# TopSheet.net
KiCad netlist of a schematic drawn in Altium Designer
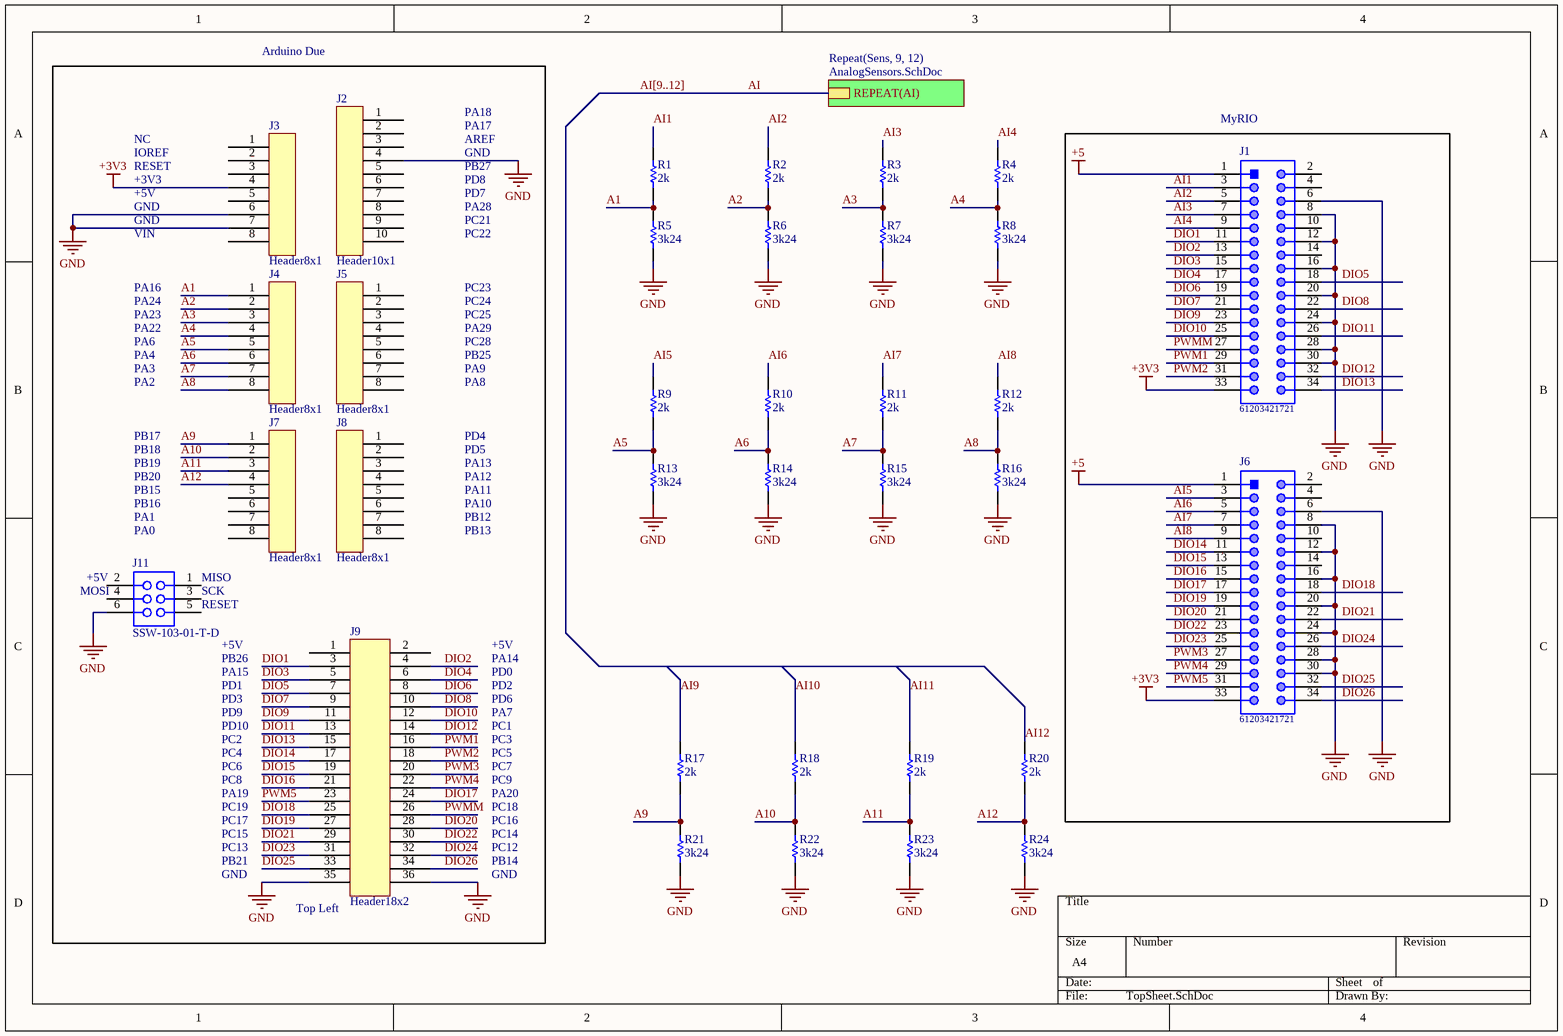
[diagram p0: TopSheet.SchDoc]

(export (version "E")
  (design (tool "Eeschema 10.0.6"))
  (components
    (comp (ref "J1")
      (value "61203421721")
      (footprint "61203421721")
      (description "Male Box Header WR-BHD, THT, Angled, pitch 2.54 mm, 34 pins")
      (fields (field (name "MANUFACTURER") "Wurth Elektronik") (field (name "PUBLISHER") "WurthElektronik"))
      (libsource (lib "Altium Content Vault") (part "WE-CN-2P-M-R34"))
    )
    (comp (ref "J2")
      (value "Header10x1")
      (footprint "Header10x1")
      (libsource (lib "Schlib1") (part "Header10x1"))
    )
    (comp (ref "J3") (value "Header8x1") (footprint "Header8x1") (libsource (lib "") (part "Header8x1_1")))
    (comp (ref "J4") (value "Header8x1") (footprint "Header8x1") (libsource (lib "") (part "Header8x1_1")))
    (comp (ref "J5")
      (value "Header8x1")
      (footprint "Header8x1")
      (libsource (lib "Schlib1") (part "Header8x1"))
    )
    (comp (ref "J6")
      (value "61203421721")
      (footprint "61203421721")
      (description "Male Box Header WR-BHD, THT, Angled, pitch 2.54 mm, 34 pins")
      (fields (field (name "MANUFACTURER") "Wurth Elektronik") (field (name "PUBLISHER") "WurthElektronik"))
      (libsource (lib "Altium Content Vault") (part "WE-CN-2P-M-R34"))
    )
    (comp (ref "J7") (value "Header8x1") (footprint "Header8x1") (libsource (lib "") (part "Header8x1_1")))
    (comp (ref "J8")
      (value "Header8x1")
      (footprint "Header8x1")
      (libsource (lib "Schlib1") (part "Header8x1"))
    )
    (comp (ref "J9")
      (value "Header18x2")
      (footprint "Header18x2")
      (libsource (lib "Schlib1") (part "Header18x2"))
    )
    (comp (ref "J11")
      (value "SSW-103-01-T-D")
      (footprint "SMTC-SSW-103-01-X-D")
      (description "SQ Post Socket, Through-hole, Vertical, -55 to 105 degC, 2.54 mm Pitch, 6-Pin, Female, RoHS")
      (fields (field (name "MANUFACTURER") "Samtec"))
      (libsource (lib "Altium Content Vault") (part "SMTC-SSW-103-01-X-D"))
    )
    (comp (ref "R1")
      (value "2k")
      (footprint "RESC1608X55X25LL10T15")
      (description "Chip Resistor, 2 KOhm, +/- 1%, 50 V, -55 to 155 degC, 0603 (1608 Metric), RoHS, Tape and Reel")
      (fields (field (name "TOLERANCE") "±1%") (field (name "MANUFACTURER") "Yageo"))
      (libsource (lib "Altium Content Vault") (part "RES-2"))
    )
    (comp (ref "R2")
      (value "2k")
      (footprint "RESC1608X55X25LL10T15")
      (description "Chip Resistor, 2 KOhm, +/- 1%, 50 V, -55 to 155 degC, 0603 (1608 Metric), RoHS, Tape and Reel")
      (fields (field (name "TOLERANCE") "±1%") (field (name "MANUFACTURER") "Yageo"))
      (libsource (lib "Altium Content Vault") (part "RES-2"))
    )
    (comp (ref "R3")
      (value "2k")
      (footprint "RESC1608X55X25LL10T15")
      (description "Chip Resistor, 2 KOhm, +/- 1%, 50 V, -55 to 155 degC, 0603 (1608 Metric), RoHS, Tape and Reel")
      (fields (field (name "TOLERANCE") "±1%") (field (name "MANUFACTURER") "Yageo"))
      (libsource (lib "Altium Content Vault") (part "RES-2"))
    )
    (comp (ref "R4")
      (value "2k")
      (footprint "RESC1608X55X25LL10T15")
      (description "Chip Resistor, 2 KOhm, +/- 1%, 50 V, -55 to 155 degC, 0603 (1608 Metric), RoHS, Tape and Reel")
      (fields (field (name "TOLERANCE") "±1%") (field (name "MANUFACTURER") "Yageo"))
      (libsource (lib "Altium Content Vault") (part "RES-2"))
    )
    (comp (ref "R5")
      (value "3k24")
      (footprint "RESC1608X55X25LL10T15")
      (fields (field (name "TOLERANCE") "±1%") (field (name "MANUFACTURER") "Yageo"))
      (libsource (lib "Altium Content Vault") (part "RES-2"))
    )
    (comp (ref "R6")
      (value "3k24")
      (footprint "RESC1608X55X25LL10T15")
      (fields (field (name "TOLERANCE") "±1%") (field (name "MANUFACTURER") "Yageo"))
      (libsource (lib "Altium Content Vault") (part "RES-2"))
    )
    (comp (ref "R7")
      (value "3k24")
      (footprint "RESC1608X55X25LL10T15")
      (fields (field (name "TOLERANCE") "±1%") (field (name "MANUFACTURER") "Yageo"))
      (libsource (lib "Altium Content Vault") (part "RES-2"))
    )
    (comp (ref "R8")
      (value "3k24")
      (footprint "RESC1608X55X25LL10T15")
      (fields (field (name "TOLERANCE") "±1%") (field (name "MANUFACTURER") "Yageo"))
      (libsource (lib "Altium Content Vault") (part "RES-2"))
    )
    (comp (ref "R9")
      (value "2k")
      (footprint "RESC1608X55X25LL10T15")
      (description "Chip Resistor, 2 KOhm, +/- 1%, 50 V, -55 to 155 degC, 0603 (1608 Metric), RoHS, Tape and Reel")
      (fields (field (name "TOLERANCE") "±1%") (field (name "MANUFACTURER") "Yageo"))
      (libsource (lib "Altium Content Vault") (part "RES-2"))
    )
    (comp (ref "R10")
      (value "2k")
      (footprint "RESC1608X55X25LL10T15")
      (description "Chip Resistor, 2 KOhm, +/- 1%, 50 V, -55 to 155 degC, 0603 (1608 Metric), RoHS, Tape and Reel")
      (fields (field (name "TOLERANCE") "±1%") (field (name "MANUFACTURER") "Yageo"))
      (libsource (lib "Altium Content Vault") (part "RES-2"))
    )
    (comp (ref "R11")
      (value "2k")
      (footprint "RESC1608X55X25LL10T15")
      (description "Chip Resistor, 2 KOhm, +/- 1%, 50 V, -55 to 155 degC, 0603 (1608 Metric), RoHS, Tape and Reel")
      (fields (field (name "TOLERANCE") "±1%") (field (name "MANUFACTURER") "Yageo"))
      (libsource (lib "Altium Content Vault") (part "RES-2"))
    )
    (comp (ref "R12")
      (value "2k")
      (footprint "RESC1608X55X25LL10T15")
      (description "Chip Resistor, 2 KOhm, +/- 1%, 50 V, -55 to 155 degC, 0603 (1608 Metric), RoHS, Tape and Reel")
      (fields (field (name "TOLERANCE") "±1%") (field (name "MANUFACTURER") "Yageo"))
      (libsource (lib "Altium Content Vault") (part "RES-2"))
    )
    (comp (ref "R13")
      (value "3k24")
      (footprint "RESC1608X55X25LL10T15")
      (fields (field (name "TOLERANCE") "±1%") (field (name "MANUFACTURER") "Yageo"))
      (libsource (lib "Altium Content Vault") (part "RES-2"))
    )
    (comp (ref "R14")
      (value "3k24")
      (footprint "RESC1608X55X25LL10T15")
      (fields (field (name "TOLERANCE") "±1%") (field (name "MANUFACTURER") "Yageo"))
      (libsource (lib "Altium Content Vault") (part "RES-2"))
    )
    (comp (ref "R15")
      (value "3k24")
      (footprint "RESC1608X55X25LL10T15")
      (fields (field (name "TOLERANCE") "±1%") (field (name "MANUFACTURER") "Yageo"))
      (libsource (lib "Altium Content Vault") (part "RES-2"))
    )
    (comp (ref "R16")
      (value "3k24")
      (footprint "RESC1608X55X25LL10T15")
      (fields (field (name "TOLERANCE") "±1%") (field (name "MANUFACTURER") "Yageo"))
      (libsource (lib "Altium Content Vault") (part "RES-2"))
    )
    (comp (ref "R17")
      (value "2k")
      (footprint "RESC1608X55X25LL10T15")
      (description "Chip Resistor, 2 KOhm, +/- 1%, 50 V, -55 to 155 degC, 0603 (1608 Metric), RoHS, Tape and Reel")
      (fields (field (name "TOLERANCE") "±1%") (field (name "MANUFACTURER") "Yageo"))
      (libsource (lib "Altium Content Vault") (part "RES-2"))
    )
    (comp (ref "R18")
      (value "2k")
      (footprint "RESC1608X55X25LL10T15")
      (description "Chip Resistor, 2 KOhm, +/- 1%, 50 V, -55 to 155 degC, 0603 (1608 Metric), RoHS, Tape and Reel")
      (fields (field (name "TOLERANCE") "±1%") (field (name "MANUFACTURER") "Yageo"))
      (libsource (lib "Altium Content Vault") (part "RES-2"))
    )
    (comp (ref "R19")
      (value "2k")
      (footprint "RESC1608X55X25LL10T15")
      (description "Chip Resistor, 2 KOhm, +/- 1%, 50 V, -55 to 155 degC, 0603 (1608 Metric), RoHS, Tape and Reel")
      (fields (field (name "TOLERANCE") "±1%") (field (name "MANUFACTURER") "Yageo"))
      (libsource (lib "Altium Content Vault") (part "RES-2"))
    )
    (comp (ref "R20")
      (value "2k")
      (footprint "RESC1608X55X25LL10T15")
      (description "Chip Resistor, 2 KOhm, +/- 1%, 50 V, -55 to 155 degC, 0603 (1608 Metric), RoHS, Tape and Reel")
      (fields (field (name "TOLERANCE") "±1%") (field (name "MANUFACTURER") "Yageo"))
      (libsource (lib "Altium Content Vault") (part "RES-2"))
    )
    (comp (ref "R21")
      (value "3k24")
      (footprint "RESC1608X55X25LL10T15")
      (fields (field (name "TOLERANCE") "±1%") (field (name "MANUFACTURER") "Yageo"))
      (libsource (lib "Altium Content Vault") (part "RES-2"))
    )
    (comp (ref "R22")
      (value "3k24")
      (footprint "RESC1608X55X25LL10T15")
      (fields (field (name "TOLERANCE") "±1%") (field (name "MANUFACTURER") "Yageo"))
      (libsource (lib "Altium Content Vault") (part "RES-2"))
    )
    (comp (ref "R23")
      (value "3k24")
      (footprint "RESC1608X55X25LL10T15")
      (fields (field (name "TOLERANCE") "±1%") (field (name "MANUFACTURER") "Yageo"))
      (libsource (lib "Altium Content Vault") (part "RES-2"))
    )
    (comp (ref "R24")
      (value "3k24")
      (footprint "RESC1608X55X25LL10T15")
      (fields (field (name "TOLERANCE") "±1%") (field (name "MANUFACTURER") "Yageo"))
      (libsource (lib "Altium Content Vault") (part "RES-2"))
    )
  )
  (nets
    (net (code "1") (name "+3V3") (class "Default")
      (node (ref "J1") (pin "33") (pinfunction "33_33") (pintype "passive"))
      (node (ref "J3") (pin "4") (pintype "passive"))
      (node (ref "J6") (pin "33") (pinfunction "33_33") (pintype "passive"))
    )
    (net (code "2") (name "+5") (class "Default")
      (node (ref "J1") (pin "1") (pinfunction "1_1") (pintype "passive"))
      (node (ref "J6") (pin "1") (pinfunction "1_1") (pintype "passive"))
    )
    (net (code "3") (name "/A1") (class "Default")
      (node (ref "J4") (pin "1") (pintype "passive"))
      (node (ref "R1") (pin "1") (pinfunction "1_1") (pintype "passive"))
      (node (ref "R5") (pin "2") (pinfunction "2_2") (pintype "passive"))
    )
    (net (code "4") (name "/A2") (class "Default")
      (node (ref "J4") (pin "2") (pintype "passive"))
      (node (ref "R2") (pin "1") (pinfunction "1_1") (pintype "passive"))
      (node (ref "R6") (pin "2") (pinfunction "2_2") (pintype "passive"))
    )
    (net (code "5") (name "/A3") (class "Default")
      (node (ref "J4") (pin "3") (pintype "passive"))
      (node (ref "R3") (pin "1") (pinfunction "1_1") (pintype "passive"))
      (node (ref "R7") (pin "2") (pinfunction "2_2") (pintype "passive"))
    )
    (net (code "6") (name "/A4") (class "Default")
      (node (ref "J4") (pin "4") (pintype "passive"))
      (node (ref "R4") (pin "1") (pinfunction "1_1") (pintype "passive"))
      (node (ref "R8") (pin "2") (pinfunction "2_2") (pintype "passive"))
    )
    (net (code "7") (name "/A5") (class "Default")
      (node (ref "J4") (pin "5") (pintype "passive"))
      (node (ref "R13") (pin "2") (pinfunction "2_2") (pintype "passive"))
      (node (ref "R9") (pin "1") (pinfunction "1_1") (pintype "passive"))
    )
    (net (code "8") (name "/A6") (class "Default")
      (node (ref "J4") (pin "6") (pintype "passive"))
      (node (ref "R10") (pin "1") (pinfunction "1_1") (pintype "passive"))
      (node (ref "R14") (pin "2") (pinfunction "2_2") (pintype "passive"))
    )
    (net (code "9") (name "/A7") (class "Default")
      (node (ref "J4") (pin "7") (pintype "passive"))
      (node (ref "R11") (pin "1") (pinfunction "1_1") (pintype "passive"))
      (node (ref "R15") (pin "2") (pinfunction "2_2") (pintype "passive"))
    )
    (net (code "10") (name "/A8") (class "Default")
      (node (ref "J4") (pin "8") (pintype "passive"))
      (node (ref "R12") (pin "1") (pinfunction "1_1") (pintype "passive"))
      (node (ref "R16") (pin "2") (pinfunction "2_2") (pintype "passive"))
    )
    (net (code "11") (name "/A9") (class "Default")
      (node (ref "J7") (pin "1") (pintype "passive"))
      (node (ref "R17") (pin "1") (pinfunction "1_1") (pintype "passive"))
      (node (ref "R21") (pin "2") (pinfunction "2_2") (pintype "passive"))
    )
    (net (code "12") (name "/A10") (class "Default")
      (node (ref "J7") (pin "2") (pintype "passive"))
      (node (ref "R18") (pin "1") (pinfunction "1_1") (pintype "passive"))
      (node (ref "R22") (pin "2") (pinfunction "2_2") (pintype "passive"))
    )
    (net (code "13") (name "/A11") (class "Default")
      (node (ref "J7") (pin "3") (pintype "passive"))
      (node (ref "R19") (pin "1") (pinfunction "1_1") (pintype "passive"))
      (node (ref "R23") (pin "2") (pinfunction "2_2") (pintype "passive"))
    )
    (net (code "14") (name "/A12") (class "Default")
      (node (ref "J7") (pin "4") (pintype "passive"))
      (node (ref "R20") (pin "1") (pinfunction "1_1") (pintype "passive"))
      (node (ref "R24") (pin "2") (pinfunction "2_2") (pintype "passive"))
    )
    (net (code "16") (name "/AI1") (class "Default")
      (node (ref "J1") (pin "3") (pinfunction "3_3") (pintype "passive"))
      (node (ref "R1") (pin "2") (pinfunction "2_2") (pintype "passive"))
    )
    (net (code "17") (name "/AI2") (class "Default")
      (node (ref "J1") (pin "5") (pinfunction "5_5") (pintype "passive"))
      (node (ref "R2") (pin "2") (pinfunction "2_2") (pintype "passive"))
    )
    (net (code "18") (name "/AI3") (class "Default")
      (node (ref "J1") (pin "7") (pinfunction "7_7") (pintype "passive"))
      (node (ref "R3") (pin "2") (pinfunction "2_2") (pintype "passive"))
    )
    (net (code "19") (name "/AI4") (class "Default")
      (node (ref "J1") (pin "9") (pinfunction "9_9") (pintype "passive"))
      (node (ref "R4") (pin "2") (pinfunction "2_2") (pintype "passive"))
    )
    (net (code "20") (name "/AI5") (class "Default")
      (node (ref "J6") (pin "3") (pinfunction "3_3") (pintype "passive"))
      (node (ref "R9") (pin "2") (pinfunction "2_2") (pintype "passive"))
    )
    (net (code "21") (name "/AI6") (class "Default")
      (node (ref "J6") (pin "5") (pinfunction "5_5") (pintype "passive"))
      (node (ref "R10") (pin "2") (pinfunction "2_2") (pintype "passive"))
    )
    (net (code "22") (name "/AI7") (class "Default")
      (node (ref "J6") (pin "7") (pinfunction "7_7") (pintype "passive"))
      (node (ref "R11") (pin "2") (pinfunction "2_2") (pintype "passive"))
    )
    (net (code "23") (name "/AI8") (class "Default")
      (node (ref "J6") (pin "9") (pinfunction "9_9") (pintype "passive"))
      (node (ref "R12") (pin "2") (pinfunction "2_2") (pintype "passive"))
    )
    (net (code "24") (name "/AI9") (class "Default")
      (node (ref "R17") (pin "2") (pinfunction "2_2") (pintype "passive"))
    )
    (net (code "25") (name "/AI10") (class "Default")
      (node (ref "R18") (pin "2") (pinfunction "2_2") (pintype "passive"))
    )
    (net (code "26") (name "/AI11") (class "Default")
      (node (ref "R19") (pin "2") (pinfunction "2_2") (pintype "passive"))
    )
    (net (code "27") (name "/AI12") (class "Default")
      (node (ref "R20") (pin "2") (pinfunction "2_2") (pintype "passive"))
    )
    (net (code "29") (name "/DIO1") (class "Default")
      (node (ref "J1") (pin "11") (pinfunction "11_11") (pintype "passive"))
      (node (ref "J9") (pin "3") (pintype "passive"))
    )
    (net (code "30") (name "/DIO2") (class "Default")
      (node (ref "J1") (pin "13") (pinfunction "13_13") (pintype "passive"))
      (node (ref "J9") (pin "4") (pintype "passive"))
    )
    (net (code "31") (name "/DIO3") (class "Default")
      (node (ref "J1") (pin "15") (pinfunction "15_15") (pintype "passive"))
      (node (ref "J9") (pin "5") (pintype "passive"))
    )
    (net (code "32") (name "/DIO4") (class "Default")
      (node (ref "J1") (pin "17") (pinfunction "17_17") (pintype "passive"))
      (node (ref "J9") (pin "6") (pintype "passive"))
    )
    (net (code "33") (name "/DIO5") (class "Default")
      (node (ref "J1") (pin "18") (pinfunction "18_18") (pintype "passive"))
      (node (ref "J9") (pin "7") (pintype "passive"))
    )
    (net (code "34") (name "/DIO6") (class "Default")
      (node (ref "J1") (pin "19") (pinfunction "19_19") (pintype "passive"))
      (node (ref "J9") (pin "8") (pintype "passive"))
    )
    (net (code "35") (name "/DIO7") (class "Default")
      (node (ref "J1") (pin "21") (pinfunction "21_21") (pintype "passive"))
      (node (ref "J9") (pin "9") (pintype "passive"))
    )
    (net (code "36") (name "/DIO8") (class "Default")
      (node (ref "J1") (pin "22") (pinfunction "22_22") (pintype "passive"))
      (node (ref "J9") (pin "10") (pintype "passive"))
    )
    (net (code "37") (name "/DIO9") (class "Default")
      (node (ref "J1") (pin "23") (pinfunction "23_23") (pintype "passive"))
      (node (ref "J9") (pin "11") (pintype "passive"))
    )
    (net (code "38") (name "/DIO10") (class "Default")
      (node (ref "J1") (pin "25") (pinfunction "25_25") (pintype "passive"))
      (node (ref "J9") (pin "12") (pintype "passive"))
    )
    (net (code "39") (name "/DIO11") (class "Default")
      (node (ref "J1") (pin "26") (pinfunction "26_26") (pintype "passive"))
      (node (ref "J9") (pin "13") (pintype "passive"))
    )
    (net (code "40") (name "/DIO12") (class "Default")
      (node (ref "J1") (pin "32") (pinfunction "32_32") (pintype "passive"))
      (node (ref "J9") (pin "14") (pintype "passive"))
    )
    (net (code "41") (name "/DIO13") (class "Default")
      (node (ref "J1") (pin "34") (pinfunction "34_34") (pintype "passive"))
      (node (ref "J9") (pin "15") (pintype "passive"))
    )
    (net (code "42") (name "/DIO14") (class "Default")
      (node (ref "J6") (pin "11") (pinfunction "11_11") (pintype "passive"))
      (node (ref "J9") (pin "17") (pintype "passive"))
    )
    (net (code "43") (name "/DIO15") (class "Default")
      (node (ref "J6") (pin "13") (pinfunction "13_13") (pintype "passive"))
      (node (ref "J9") (pin "19") (pintype "passive"))
    )
    (net (code "44") (name "/DIO16") (class "Default")
      (node (ref "J6") (pin "15") (pinfunction "15_15") (pintype "passive"))
      (node (ref "J9") (pin "21") (pintype "passive"))
    )
    (net (code "45") (name "/DIO17") (class "Default")
      (node (ref "J6") (pin "17") (pinfunction "17_17") (pintype "passive"))
      (node (ref "J9") (pin "24") (pintype "passive"))
    )
    (net (code "46") (name "/DIO18") (class "Default")
      (node (ref "J6") (pin "18") (pinfunction "18_18") (pintype "passive"))
      (node (ref "J9") (pin "25") (pintype "passive"))
    )
    (net (code "47") (name "/DIO19") (class "Default")
      (node (ref "J6") (pin "19") (pinfunction "19_19") (pintype "passive"))
      (node (ref "J9") (pin "27") (pintype "passive"))
    )
    (net (code "48") (name "/DIO20") (class "Default")
      (node (ref "J6") (pin "21") (pinfunction "21_21") (pintype "passive"))
      (node (ref "J9") (pin "28") (pintype "passive"))
    )
    (net (code "49") (name "/DIO21") (class "Default")
      (node (ref "J6") (pin "22") (pinfunction "22_22") (pintype "passive"))
      (node (ref "J9") (pin "29") (pintype "passive"))
    )
    (net (code "50") (name "/DIO22") (class "Default")
      (node (ref "J6") (pin "23") (pinfunction "23_23") (pintype "passive"))
      (node (ref "J9") (pin "30") (pintype "passive"))
    )
    (net (code "51") (name "/DIO23") (class "Default")
      (node (ref "J6") (pin "25") (pinfunction "25_25") (pintype "passive"))
      (node (ref "J9") (pin "31") (pintype "passive"))
    )
    (net (code "52") (name "/DIO24") (class "Default")
      (node (ref "J6") (pin "26") (pinfunction "26_26") (pintype "passive"))
      (node (ref "J9") (pin "32") (pintype "passive"))
    )
    (net (code "53") (name "/DIO25") (class "Default")
      (node (ref "J6") (pin "32") (pinfunction "32_32") (pintype "passive"))
      (node (ref "J9") (pin "33") (pintype "passive"))
    )
    (net (code "54") (name "/DIO26") (class "Default")
      (node (ref "J6") (pin "34") (pinfunction "34_34") (pintype "passive"))
      (node (ref "J9") (pin "34") (pintype "passive"))
    )
    (net (code "55") (name "/PWM1") (class "Default")
      (node (ref "J1") (pin "29") (pinfunction "29_29") (pintype "passive"))
      (node (ref "J9") (pin "16") (pintype "passive"))
    )
    (net (code "56") (name "/PWM2") (class "Default")
      (node (ref "J1") (pin "31") (pinfunction "31_31") (pintype "passive"))
      (node (ref "J9") (pin "18") (pintype "passive"))
    )
    (net (code "57") (name "/PWM3") (class "Default")
      (node (ref "J6") (pin "27") (pinfunction "27_27") (pintype "passive"))
      (node (ref "J9") (pin "20") (pintype "passive"))
    )
    (net (code "58") (name "/PWM4") (class "Default")
      (node (ref "J6") (pin "29") (pinfunction "29_29") (pintype "passive"))
      (node (ref "J9") (pin "22") (pintype "passive"))
    )
    (net (code "59") (name "/PWM5") (class "Default")
      (node (ref "J6") (pin "31") (pinfunction "31_31") (pintype "passive"))
      (node (ref "J9") (pin "23") (pintype "passive"))
    )
    (net (code "60") (name "/PWMM") (class "Default")
      (node (ref "J1") (pin "27") (pinfunction "27_27") (pintype "passive"))
      (node (ref "J9") (pin "26") (pintype "passive"))
    )
    (net (code "61") (name "GND") (class "Default")
      (node (ref "J1") (pin "12") (pinfunction "12_12") (pintype "passive"))
      (node (ref "J1") (pin "16") (pinfunction "16_16") (pintype "passive"))
      (node (ref "J1") (pin "20") (pinfunction "20_20") (pintype "passive"))
      (node (ref "J1") (pin "24") (pinfunction "24_24") (pintype "passive"))
      (node (ref "J1") (pin "28") (pinfunction "28_28") (pintype "passive"))
      (node (ref "J1") (pin "30") (pinfunction "30_30") (pintype "passive"))
      (node (ref "J1") (pin "6") (pinfunction "6_6") (pintype "passive"))
      (node (ref "J1") (pin "8") (pinfunction "8_8") (pintype "passive"))
      (node (ref "J11") (pin "6") (pinfunction "2_6") (pintype "passive"))
      (node (ref "J2") (pin "4") (pintype "passive"))
      (node (ref "J3") (pin "6") (pintype "passive"))
      (node (ref "J3") (pin "7") (pintype "passive"))
      (node (ref "J6") (pin "12") (pinfunction "12_12") (pintype "passive"))
      (node (ref "J6") (pin "16") (pinfunction "16_16") (pintype "passive"))
      (node (ref "J6") (pin "20") (pinfunction "20_20") (pintype "passive"))
      (node (ref "J6") (pin "24") (pinfunction "24_24") (pintype "passive"))
      (node (ref "J6") (pin "28") (pinfunction "28_28") (pintype "passive"))
      (node (ref "J6") (pin "30") (pinfunction "30_30") (pintype "passive"))
      (node (ref "J6") (pin "6") (pinfunction "6_6") (pintype "passive"))
      (node (ref "J6") (pin "8") (pinfunction "8_8") (pintype "passive"))
      (node (ref "J9") (pin "35") (pintype "passive"))
      (node (ref "J9") (pin "36") (pintype "passive"))
      (node (ref "R13") (pin "1") (pinfunction "1_1") (pintype "passive"))
      (node (ref "R14") (pin "1") (pinfunction "1_1") (pintype "passive"))
      (node (ref "R15") (pin "1") (pinfunction "1_1") (pintype "passive"))
      (node (ref "R16") (pin "1") (pinfunction "1_1") (pintype "passive"))
      (node (ref "R21") (pin "1") (pinfunction "1_1") (pintype "passive"))
      (node (ref "R22") (pin "1") (pinfunction "1_1") (pintype "passive"))
      (node (ref "R23") (pin "1") (pinfunction "1_1") (pintype "passive"))
      (node (ref "R24") (pin "1") (pinfunction "1_1") (pintype "passive"))
      (node (ref "R5") (pin "1") (pinfunction "1_1") (pintype "passive"))
      (node (ref "R6") (pin "1") (pinfunction "1_1") (pintype "passive"))
      (node (ref "R7") (pin "1") (pinfunction "1_1") (pintype "passive"))
      (node (ref "R8") (pin "1") (pinfunction "1_1") (pintype "passive"))
    )
    (net (code "62") (name "unconnected-(J1-Pad2)") (class "Default")
      (node (ref "J1") (pin "2") (pinfunction "2_2") (pintype "passive"))
    )
    (net (code "63") (name "unconnected-(J1-Pad4)") (class "Default")
      (node (ref "J1") (pin "4") (pinfunction "4_4") (pintype "passive"))
    )
    (net (code "64") (name "unconnected-(J1-Pad10)") (class "Default")
      (node (ref "J1") (pin "10") (pinfunction "10_10") (pintype "passive"))
    )
    (net (code "65") (name "unconnected-(J1-Pad14)") (class "Default")
      (node (ref "J1") (pin "14") (pinfunction "14_14") (pintype "passive"))
    )
    (net (code "66") (name "unconnected-(J2-Pad1)") (class "Default")
      (node (ref "J2") (pin "1") (pintype "passive"))
    )
    (net (code "67") (name "unconnected-(J2-Pad2)") (class "Default")
      (node (ref "J2") (pin "2") (pintype "passive"))
    )
    (net (code "68") (name "unconnected-(J2-Pad3)") (class "Default")
      (node (ref "J2") (pin "3") (pintype "passive"))
    )
    (net (code "69") (name "unconnected-(J2-Pad5)") (class "Default")
      (node (ref "J2") (pin "5") (pintype "passive"))
    )
    (net (code "70") (name "unconnected-(J2-Pad6)") (class "Default")
      (node (ref "J2") (pin "6") (pintype "passive"))
    )
    (net (code "71") (name "unconnected-(J2-Pad7)") (class "Default")
      (node (ref "J2") (pin "7") (pintype "passive"))
    )
    (net (code "72") (name "unconnected-(J2-Pad8)") (class "Default")
      (node (ref "J2") (pin "8") (pintype "passive"))
    )
    (net (code "73") (name "unconnected-(J2-Pad9)") (class "Default")
      (node (ref "J2") (pin "9") (pintype "passive"))
    )
    (net (code "74") (name "unconnected-(J2-Pad10)") (class "Default")
      (node (ref "J2") (pin "10") (pintype "passive"))
    )
    (net (code "75") (name "unconnected-(J3-Pad1)") (class "Default")
      (node (ref "J3") (pin "1") (pintype "passive"))
    )
    (net (code "76") (name "unconnected-(J3-Pad2)") (class "Default")
      (node (ref "J3") (pin "2") (pintype "passive"))
    )
    (net (code "77") (name "unconnected-(J3-Pad3)") (class "Default")
      (node (ref "J3") (pin "3") (pintype "passive"))
    )
    (net (code "78") (name "unconnected-(J3-Pad5)") (class "Default")
      (node (ref "J3") (pin "5") (pintype "passive"))
    )
    (net (code "79") (name "unconnected-(J3-Pad8)") (class "Default")
      (node (ref "J3") (pin "8") (pintype "passive"))
    )
    (net (code "80") (name "unconnected-(J5-Pad1)") (class "Default")
      (node (ref "J5") (pin "1") (pintype "passive"))
    )
    (net (code "81") (name "unconnected-(J5-Pad2)") (class "Default")
      (node (ref "J5") (pin "2") (pintype "passive"))
    )
    (net (code "82") (name "unconnected-(J5-Pad3)") (class "Default")
      (node (ref "J5") (pin "3") (pintype "passive"))
    )
    (net (code "83") (name "unconnected-(J5-Pad4)") (class "Default")
      (node (ref "J5") (pin "4") (pintype "passive"))
    )
    (net (code "84") (name "unconnected-(J5-Pad5)") (class "Default")
      (node (ref "J5") (pin "5") (pintype "passive"))
    )
    (net (code "85") (name "unconnected-(J5-Pad6)") (class "Default")
      (node (ref "J5") (pin "6") (pintype "passive"))
    )
    (net (code "86") (name "unconnected-(J5-Pad7)") (class "Default")
      (node (ref "J5") (pin "7") (pintype "passive"))
    )
    (net (code "87") (name "unconnected-(J5-Pad8)") (class "Default")
      (node (ref "J5") (pin "8") (pintype "passive"))
    )
    (net (code "88") (name "unconnected-(J6-Pad2)") (class "Default")
      (node (ref "J6") (pin "2") (pinfunction "2_2") (pintype "passive"))
    )
    (net (code "89") (name "unconnected-(J6-Pad4)") (class "Default")
      (node (ref "J6") (pin "4") (pinfunction "4_4") (pintype "passive"))
    )
    (net (code "90") (name "unconnected-(J6-Pad10)") (class "Default")
      (node (ref "J6") (pin "10") (pinfunction "10_10") (pintype "passive"))
    )
    (net (code "91") (name "unconnected-(J6-Pad14)") (class "Default")
      (node (ref "J6") (pin "14") (pinfunction "14_14") (pintype "passive"))
    )
    (net (code "92") (name "unconnected-(J7-Pad5)") (class "Default")
      (node (ref "J7") (pin "5") (pintype "passive"))
    )
    (net (code "93") (name "unconnected-(J7-Pad6)") (class "Default")
      (node (ref "J7") (pin "6") (pintype "passive"))
    )
    (net (code "94") (name "unconnected-(J7-Pad7)") (class "Default")
      (node (ref "J7") (pin "7") (pintype "passive"))
    )
    (net (code "95") (name "unconnected-(J7-Pad8)") (class "Default")
      (node (ref "J7") (pin "8") (pintype "passive"))
    )
    (net (code "96") (name "unconnected-(J8-Pad1)") (class "Default")
      (node (ref "J8") (pin "1") (pintype "passive"))
    )
    (net (code "97") (name "unconnected-(J8-Pad2)") (class "Default")
      (node (ref "J8") (pin "2") (pintype "passive"))
    )
    (net (code "98") (name "unconnected-(J8-Pad3)") (class "Default")
      (node (ref "J8") (pin "3") (pintype "passive"))
    )
    (net (code "99") (name "unconnected-(J8-Pad4)") (class "Default")
      (node (ref "J8") (pin "4") (pintype "passive"))
    )
    (net (code "100") (name "unconnected-(J8-Pad5)") (class "Default")
      (node (ref "J8") (pin "5") (pintype "passive"))
    )
    (net (code "101") (name "unconnected-(J8-Pad6)") (class "Default")
      (node (ref "J8") (pin "6") (pintype "passive"))
    )
    (net (code "102") (name "unconnected-(J8-Pad7)") (class "Default")
      (node (ref "J8") (pin "7") (pintype "passive"))
    )
    (net (code "103") (name "unconnected-(J8-Pad8)") (class "Default")
      (node (ref "J8") (pin "8") (pintype "passive"))
    )
    (net (code "104") (name "unconnected-(J9-Pad1)") (class "Default")
      (node (ref "J9") (pin "1") (pintype "passive"))
    )
    (net (code "105") (name "unconnected-(J9-Pad2)") (class "Default")
      (node (ref "J9") (pin "2") (pintype "passive"))
    )
    (net (code "106") (name "unconnected-(J11-1-Pad5)") (class "Default")
      (node (ref "J11") (pin "5") (pinfunction "1_5") (pintype "passive"))
    )
    (net (code "107") (name "unconnected-(J11-5-Pad1)") (class "Default")
      (node (ref "J11") (pin "1") (pinfunction "5_1") (pintype "passive"))
    )
    (net (code "108") (name "unconnected-(J11-6-Pad2)") (class "Default")
      (node (ref "J11") (pin "2") (pinfunction "6_2") (pintype "passive"))
    )
    (net (code "109") (name "unconnected-(J11-Pad3)") (class "Default")
      (node (ref "J11") (pin "3") (pinfunction "3_3") (pintype "passive"))
    )
    (net (code "110") (name "unconnected-(J11-Pad4)") (class "Default")
      (node (ref "J11") (pin "4") (pinfunction "4_4") (pintype "passive"))
    )
  )
)
